# main.net
KiCad netlist of a schematic drawn in Altium Designer
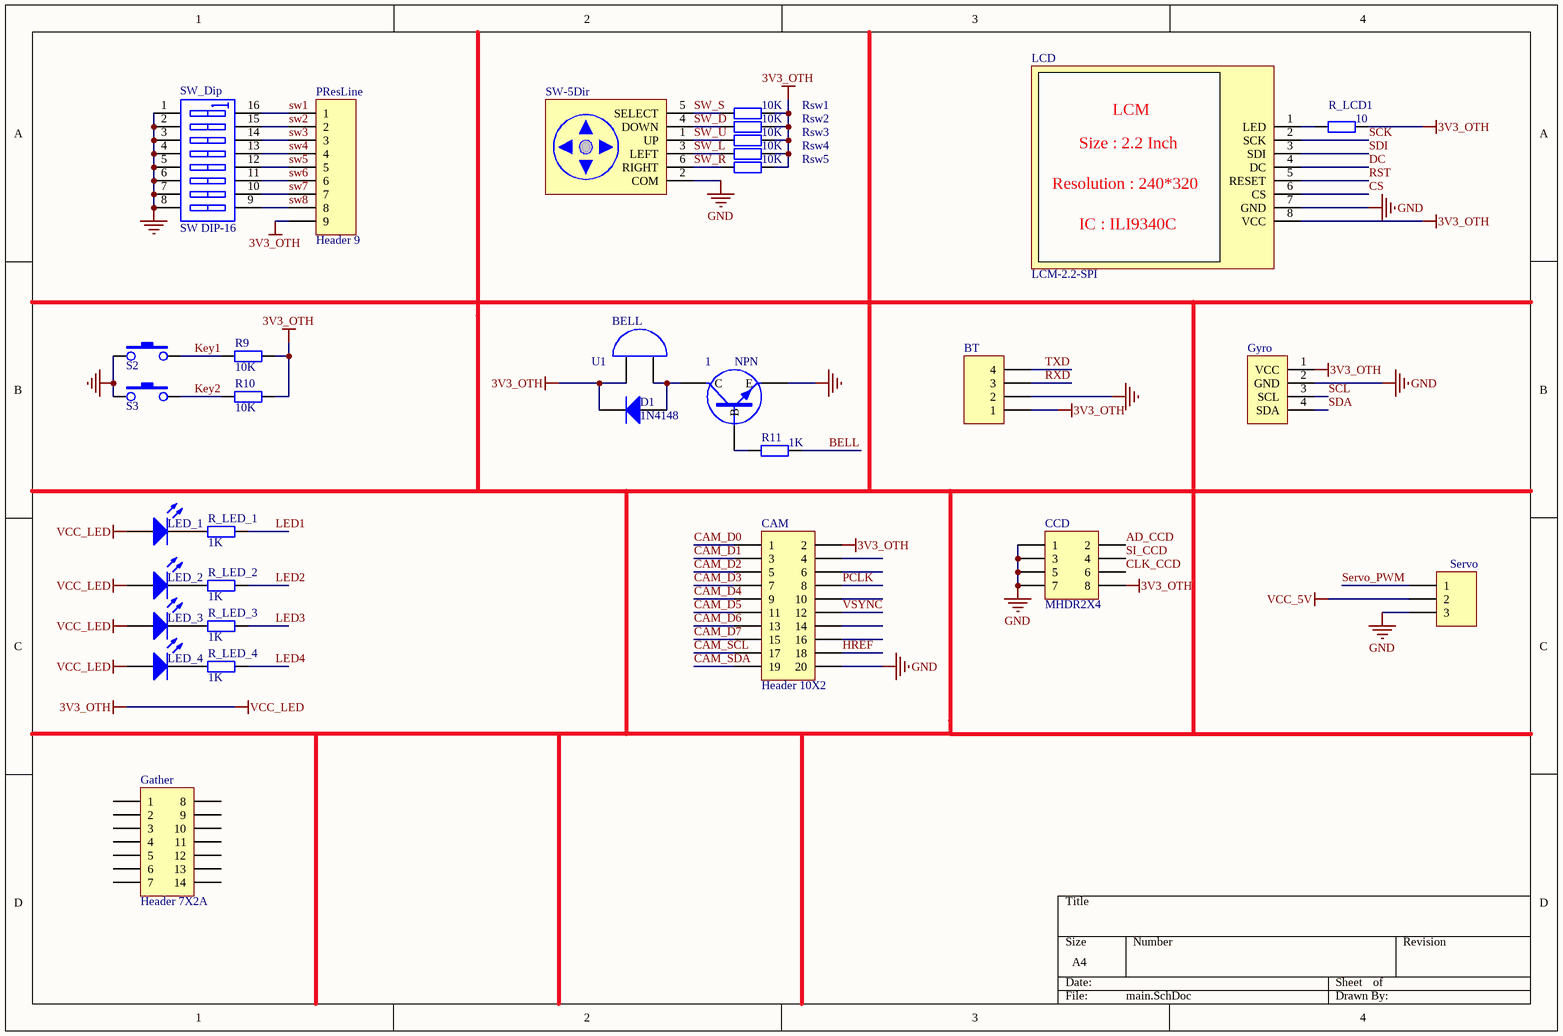
[diagram p0: main.SchDoc]

(export (version "E")
  (design (tool "Eeschema 10.0.6"))
  (components
    (comp (ref "1") (value "NPN") (footprint "BEC_123_S") (libsource (lib "lichao_Library") (part "NPN")))
    (comp (ref "BT")
      (value "Header 4")
      (footprint "HDR1X4")
      (description "Header, 4-Pin")
      (fields (field (name "PUBLISHER") "Altium Limited"))
      (libsource (lib "Miscellaneous Connectors") (part "Header 4"))
    )
    (comp (ref "CAM")
      (value "Header 10X2")
      (footprint "Camer")
      (description "Header, 10-Pin, Dual row")
      (fields (field (name "PUBLISHER") "Altium Limited"))
      (libsource (lib "Miscellaneous Connectors") (part "Header 10X2"))
    )
    (comp (ref "CCD")
      (value "MHDR2X4")
      (footprint "CCD")
      (description "Header, 4-Pin, Dual row")
      (fields (field (name "PUBLISHER") "Altium Limited"))
      (libsource (lib "lichao_Library") (part "MHDR2X4"))
    )
    (comp (ref "D1")
      (value "1N4148")
      (footprint "1N4148")
      (fields (field (name "PUBLISHER") "Altium Limited"))
      (libsource (lib "YMYPcbLib") (part "Diode"))
    )
    (comp (ref "Gather")
      (value "Header 7X2A")
      (footprint "HDR2X7_CEN")
      (description "Header, 7-Pin, Dual row")
      (fields (field (name "PUBLISHER") "Altium Limited"))
      (libsource (lib "Miscellaneous Connectors") (part "Header 7X2A"))
    )
    (comp (ref "Gyro") (value "Gyro") (footprint "GYRO") (libsource (lib "lichao_Library") (part "Gyro")))
    (comp (ref "LCD")
      (value "LCM-2.2-SPI")
      (footprint "LCD")
      (description "LCM 2.2inch SPI")
      (fields (field (name "PUBLISHER") "Altium Limited"))
      (libsource (lib "mine") (part "LCM-2.2-SPI"))
    )
    (comp (ref "LED_1")
      (value "LED")
      (footprint "0805-S")
      (description "Typical INFRARED GaAs LED")
      (fields (field (name "PUBLISHER") "Altium Limited"))
      (libsource (lib "Miscellaneous Devices") (part "LED0"))
    )
    (comp (ref "LED_2")
      (value "LED")
      (footprint "0805-S")
      (description "Typical INFRARED GaAs LED")
      (fields (field (name "PUBLISHER") "Altium Limited"))
      (libsource (lib "Miscellaneous Devices") (part "LED0"))
    )
    (comp (ref "LED_3")
      (value "LED")
      (footprint "0805-S")
      (description "Typical INFRARED GaAs LED")
      (fields (field (name "PUBLISHER") "Altium Limited"))
      (libsource (lib "Miscellaneous Devices") (part "LED0"))
    )
    (comp (ref "LED_4")
      (value "LED")
      (footprint "0805-S")
      (description "Typical INFRARED GaAs LED")
      (fields (field (name "PUBLISHER") "Altium Limited"))
      (libsource (lib "Miscellaneous Devices") (part "LED0"))
    )
    (comp (ref "PResLine")
      (value "Header 9")
      (footprint "HDR1X9")
      (description "Header, 9-Pin")
      (fields (field (name "PUBLISHER") "Altium Limited"))
      (libsource (lib "Miscellaneous Connectors") (part "Header 9"))
    )
    (comp (ref "R9")
      (value "10K")
      (footprint "0805-S")
      (description "Resistor")
      (fields (field (name "PUBLISHER") "Altium Limited"))
      (libsource (lib "") (part "Res2_1"))
    )
    (comp (ref "R10")
      (value "10K")
      (footprint "0805-S")
      (description "Resistor")
      (fields (field (name "PUBLISHER") "Altium Limited"))
      (libsource (lib "") (part "Res2_1"))
    )
    (comp (ref "R11")
      (value "1K")
      (footprint "0805-S")
      (description "Resistor")
      (fields (field (name "PUBLISHER") "Altium Limited"))
      (libsource (lib "Miscellaneous Devices") (part "Res2"))
    )
    (comp (ref "Rsw1")
      (value "10K")
      (footprint "0805-S")
      (description "Resistor")
      (fields (field (name "PUBLISHER") "Altium Limited"))
      (libsource (lib "Miscellaneous Devices") (part "Res2"))
    )
    (comp (ref "Rsw2")
      (value "10K")
      (footprint "0805-S")
      (description "Resistor")
      (fields (field (name "PUBLISHER") "Altium Limited"))
      (libsource (lib "Miscellaneous Devices") (part "Res2"))
    )
    (comp (ref "Rsw3")
      (value "10K")
      (footprint "0805-S")
      (description "Resistor")
      (fields (field (name "PUBLISHER") "Altium Limited"))
      (libsource (lib "Miscellaneous Devices") (part "Res2"))
    )
    (comp (ref "Rsw4")
      (value "10K")
      (footprint "0805-S")
      (description "Resistor")
      (fields (field (name "PUBLISHER") "Altium Limited"))
      (libsource (lib "Miscellaneous Devices") (part "Res2"))
    )
    (comp (ref "Rsw5")
      (value "10K")
      (footprint "0805-S")
      (description "Resistor")
      (fields (field (name "PUBLISHER") "Altium Limited"))
      (libsource (lib "Miscellaneous Devices") (part "Res2"))
    )
    (comp (ref "R_LCD1")
      (value "10")
      (footprint "0805-S")
      (description "Resistor")
      (fields (field (name "PUBLISHER") "Altium Limited"))
      (libsource (lib "") (part "Res2_1"))
    )
    (comp (ref "R_LED_1")
      (value "1K")
      (footprint "0805-S")
      (description "Resistor")
      (fields (field (name "PUBLISHER") "Altium Limited"))
      (libsource (lib "") (part "Res2_2"))
    )
    (comp (ref "R_LED_2")
      (value "1K")
      (footprint "0805-S")
      (description "Resistor")
      (fields (field (name "PUBLISHER") "Altium Limited"))
      (libsource (lib "") (part "Res2_2"))
    )
    (comp (ref "R_LED_3")
      (value "1K")
      (footprint "0805-S")
      (description "Resistor")
      (fields (field (name "PUBLISHER") "Altium Limited"))
      (libsource (lib "") (part "Res2_2"))
    )
    (comp (ref "R_LED_4")
      (value "1K")
      (footprint "0805-S")
      (description "Resistor")
      (fields (field (name "PUBLISHER") "Altium Limited"))
      (libsource (lib "") (part "Res2_2"))
    )
    (comp (ref "S2") (value "SW-PB") (footprint "key-press") (libsource (lib "*") (part "SW-PB")))
    (comp (ref "S3") (value "SW-PB") (footprint "key-press") (libsource (lib "*") (part "SW-PB")))
    (comp (ref "Servo")
      (value "Ser_head")
      (footprint "HDR1X3")
      (description "Header, 3-Pin")
      (fields (field (name "PUBLISHER") "Altium Limited"))
      (libsource (lib "Miscellaneous Connectors") (part "Header 3"))
    )
    (comp (ref "SW-5Dir")
      (value "SW-5dir")
      (footprint "SW-5dir")
      (description "2pin_GND")
      (fields (field (name "PUBLISHER") "Altium Limited"))
      (libsource (lib "lichao_Library") (part "SW-5dir"))
    )
    (comp (ref "SW_Dip")
      (value "SW DIP-16")
      (footprint "DIP16")
      (description "DIP Switch, 8 Position, SPST")
      (fields (field (name "PUBLISHER") "Altium Limited"))
      (libsource (lib "Miscellaneous Devices") (part "SW DIP-8"))
    )
    (comp (ref "U1")
      (value "BELL")
      (footprint "BEEP")
      (description "Bell")
      (libsource (lib "*") (part "BELL"))
    )
  )
  (nets
    (net (code "1") (name "/AD_CCD") (class "Default")
      (node (ref "CCD") (pin "2") (pinfunction "2_2") (pintype "passive"))
    )
    (net (code "2") (name "/BELL") (class "Default")
      (node (ref "R11") (pin "2") (pinfunction "2_2") (pintype "passive"))
    )
    (net (code "3") (name "/CAM_D0") (class "Default")
      (node (ref "CAM") (pin "1") (pinfunction "1_1") (pintype "passive"))
    )
    (net (code "4") (name "/CAM_D1") (class "Default")
      (node (ref "CAM") (pin "3") (pinfunction "3_3") (pintype "passive"))
    )
    (net (code "5") (name "/CAM_D2") (class "Default")
      (node (ref "CAM") (pin "5") (pinfunction "5_5") (pintype "passive"))
    )
    (net (code "6") (name "/CAM_D3") (class "Default")
      (node (ref "CAM") (pin "7") (pinfunction "7_7") (pintype "passive"))
    )
    (net (code "7") (name "/CAM_D4") (class "Default")
      (node (ref "CAM") (pin "9") (pinfunction "9_9") (pintype "passive"))
    )
    (net (code "8") (name "/CAM_D5") (class "Default")
      (node (ref "CAM") (pin "11") (pinfunction "11_11") (pintype "passive"))
    )
    (net (code "9") (name "/CAM_D6") (class "Default")
      (node (ref "CAM") (pin "13") (pinfunction "13_13") (pintype "passive"))
    )
    (net (code "10") (name "/CAM_D7") (class "Default")
      (node (ref "CAM") (pin "15") (pinfunction "15_15") (pintype "passive"))
    )
    (net (code "11") (name "/CAM_SCL") (class "Default")
      (node (ref "CAM") (pin "17") (pinfunction "17_17") (pintype "passive"))
    )
    (net (code "12") (name "/CAM_SDA") (class "Default")
      (node (ref "CAM") (pin "19") (pinfunction "19_19") (pintype "passive"))
    )
    (net (code "13") (name "/CLK_CCD") (class "Default")
      (node (ref "CCD") (pin "6") (pinfunction "6_6") (pintype "passive"))
    )
    (net (code "14") (name "/CS") (class "Default")
      (node (ref "LCD") (pin "6") (pinfunction "CS_6") (pintype "passive"))
    )
    (net (code "15") (name "/DC") (class "Default")
      (node (ref "LCD") (pin "4") (pinfunction "DC_4") (pintype "passive"))
    )
    (net (code "16") (name "/HREF") (class "Default")
      (node (ref "CAM") (pin "18") (pinfunction "18_18") (pintype "passive"))
    )
    (net (code "17") (name "/Key1") (class "Default")
      (node (ref "R9") (pin "2") (pinfunction "2_2") (pintype "passive"))
      (node (ref "S2") (pin "2") (pinfunction "2_2") (pintype "passive"))
    )
    (net (code "18") (name "/Key2") (class "Default")
      (node (ref "R10") (pin "2") (pinfunction "2_2") (pintype "passive"))
      (node (ref "S3") (pin "2") (pinfunction "2_2") (pintype "passive"))
    )
    (net (code "19") (name "/LED1") (class "Default")
      (node (ref "R_LED_1") (pin "1") (pinfunction "1_1") (pintype "passive"))
    )
    (net (code "20") (name "/LED2") (class "Default")
      (node (ref "R_LED_2") (pin "1") (pinfunction "1_1") (pintype "passive"))
    )
    (net (code "21") (name "/LED3") (class "Default")
      (node (ref "R_LED_3") (pin "1") (pinfunction "1_1") (pintype "passive"))
    )
    (net (code "22") (name "/LED4") (class "Default")
      (node (ref "R_LED_4") (pin "1") (pinfunction "1_1") (pintype "passive"))
    )
    (net (code "23") (name "/PCLK") (class "Default")
      (node (ref "CAM") (pin "8") (pinfunction "8_8") (pintype "passive"))
    )
    (net (code "24") (name "/RST") (class "Default")
      (node (ref "LCD") (pin "5") (pinfunction "RESET_5") (pintype "passive"))
    )
    (net (code "25") (name "/RXD") (class "Default")
      (node (ref "BT") (pin "3") (pinfunction "3_3") (pintype "passive"))
    )
    (net (code "26") (name "/SCK") (class "Default")
      (node (ref "LCD") (pin "2") (pinfunction "SCK_2") (pintype "passive"))
    )
    (net (code "27") (name "/SCL") (class "Default")
      (node (ref "Gyro") (pin "3") (pinfunction "SCL_3") (pintype "passive"))
    )
    (net (code "28") (name "/SDA") (class "Default")
      (node (ref "Gyro") (pin "4") (pinfunction "SDA_4") (pintype "passive"))
    )
    (net (code "29") (name "/SDI") (class "Default")
      (node (ref "LCD") (pin "3") (pinfunction "SDI_3") (pintype "passive"))
    )
    (net (code "30") (name "/SI_CCD") (class "Default")
      (node (ref "CCD") (pin "4") (pinfunction "4_4") (pintype "passive"))
    )
    (net (code "31") (name "/SW_D") (class "Default")
      (node (ref "Rsw2") (pin "1") (pinfunction "1_1") (pintype "passive"))
      (node (ref "SW-5Dir") (pin "4") (pinfunction "DOWN_4") (pintype "passive"))
    )
    (net (code "32") (name "/SW_L") (class "Default")
      (node (ref "Rsw4") (pin "1") (pinfunction "1_1") (pintype "passive"))
      (node (ref "SW-5Dir") (pin "3") (pinfunction "LEFT_3") (pintype "passive"))
    )
    (net (code "33") (name "/SW_R") (class "Default")
      (node (ref "Rsw5") (pin "1") (pinfunction "1_1") (pintype "passive"))
      (node (ref "SW-5Dir") (pin "6") (pinfunction "RIGHT_6") (pintype "passive"))
    )
    (net (code "34") (name "/SW_S") (class "Default")
      (node (ref "Rsw1") (pin "1") (pinfunction "1_1") (pintype "passive"))
      (node (ref "SW-5Dir") (pin "5") (pinfunction "SELECT_5") (pintype "passive"))
    )
    (net (code "35") (name "/SW_U") (class "Default")
      (node (ref "Rsw3") (pin "1") (pinfunction "1_1") (pintype "passive"))
      (node (ref "SW-5Dir") (pin "1") (pinfunction "UP_1") (pintype "passive"))
    )
    (net (code "36") (name "/Servo_PWM") (class "Default")
      (node (ref "Servo") (pin "1") (pinfunction "1_1") (pintype "passive"))
    )
    (net (code "37") (name "/TXD") (class "Default")
      (node (ref "BT") (pin "4") (pinfunction "4_4") (pintype "passive"))
    )
    (net (code "38") (name "/VSYNC") (class "Default")
      (node (ref "CAM") (pin "12") (pinfunction "12_12") (pintype "passive"))
    )
    (net (code "39") (name "/sw1") (class "Default")
      (node (ref "PResLine") (pin "1") (pinfunction "1_1") (pintype "passive"))
      (node (ref "SW_Dip") (pin "16") (pinfunction "B1_16") (pintype "passive"))
    )
    (net (code "40") (name "/sw2") (class "Default")
      (node (ref "PResLine") (pin "2") (pinfunction "2_2") (pintype "passive"))
      (node (ref "SW_Dip") (pin "15") (pinfunction "B2_15") (pintype "passive"))
    )
    (net (code "41") (name "/sw3") (class "Default")
      (node (ref "PResLine") (pin "3") (pinfunction "3_3") (pintype "passive"))
      (node (ref "SW_Dip") (pin "14") (pinfunction "B3_14") (pintype "passive"))
    )
    (net (code "42") (name "/sw4") (class "Default")
      (node (ref "PResLine") (pin "4") (pinfunction "4_4") (pintype "passive"))
      (node (ref "SW_Dip") (pin "13") (pinfunction "B4_13") (pintype "passive"))
    )
    (net (code "43") (name "/sw5") (class "Default")
      (node (ref "PResLine") (pin "5") (pinfunction "5_5") (pintype "passive"))
      (node (ref "SW_Dip") (pin "12") (pinfunction "B5_12") (pintype "passive"))
    )
    (net (code "44") (name "/sw6") (class "Default")
      (node (ref "PResLine") (pin "6") (pinfunction "6_6") (pintype "passive"))
      (node (ref "SW_Dip") (pin "11") (pinfunction "B6_11") (pintype "passive"))
    )
    (net (code "45") (name "/sw7") (class "Default")
      (node (ref "PResLine") (pin "7") (pinfunction "7_7") (pintype "passive"))
      (node (ref "SW_Dip") (pin "10") (pinfunction "B7_10") (pintype "passive"))
    )
    (net (code "46") (name "/sw8") (class "Default")
      (node (ref "PResLine") (pin "8") (pinfunction "8_8") (pintype "passive"))
      (node (ref "SW_Dip") (pin "9") (pinfunction "B8_9") (pintype "passive"))
    )
    (net (code "47") (name "3V3_OTH") (class "Default")
      (node (ref "BT") (pin "1") (pinfunction "1_1") (pintype "passive"))
      (node (ref "CAM") (pin "2") (pinfunction "2_2") (pintype "passive"))
      (node (ref "CCD") (pin "8") (pinfunction "8_8") (pintype "passive"))
      (node (ref "D1") (pin "2") (pinfunction "K_2") (pintype "passive"))
      (node (ref "Gyro") (pin "1") (pinfunction "VCC_1") (pintype "passive"))
      (node (ref "LCD") (pin "8") (pinfunction "VCC_8") (pintype "passive"))
      (node (ref "LED_1") (pin "1") (pinfunction "A_1") (pintype "passive"))
      (node (ref "LED_2") (pin "1") (pinfunction "A_1") (pintype "passive"))
      (node (ref "LED_3") (pin "1") (pinfunction "A_1") (pintype "passive"))
      (node (ref "LED_4") (pin "1") (pinfunction "A_1") (pintype "passive"))
      (node (ref "PResLine") (pin "9") (pinfunction "9_9") (pintype "passive"))
      (node (ref "R10") (pin "1") (pinfunction "1_1") (pintype "passive"))
      (node (ref "R9") (pin "1") (pinfunction "1_1") (pintype "passive"))
      (node (ref "R_LCD1") (pin "1") (pinfunction "1_1") (pintype "passive"))
      (node (ref "Rsw1") (pin "2") (pinfunction "2_2") (pintype "passive"))
      (node (ref "Rsw2") (pin "2") (pinfunction "2_2") (pintype "passive"))
      (node (ref "Rsw3") (pin "2") (pinfunction "2_2") (pintype "passive"))
      (node (ref "Rsw4") (pin "2") (pinfunction "2_2") (pintype "passive"))
      (node (ref "Rsw5") (pin "2") (pinfunction "2_2") (pintype "passive"))
      (node (ref "U1") (pin "1") (pinfunction "A_1") (pintype "passive"))
    )
    (net (code "48") (name "GND") (class "Default")
      (node (ref "1") (pin "2") (pinfunction "E_2") (pintype "passive"))
      (node (ref "BT") (pin "2") (pinfunction "2_2") (pintype "passive"))
      (node (ref "CAM") (pin "20") (pinfunction "20_20") (pintype "passive"))
      (node (ref "CCD") (pin "1") (pinfunction "1_1") (pintype "passive"))
      (node (ref "CCD") (pin "3") (pinfunction "3_3") (pintype "passive"))
      (node (ref "CCD") (pin "5") (pinfunction "5_5") (pintype "passive"))
      (node (ref "CCD") (pin "7") (pinfunction "7_7") (pintype "passive"))
      (node (ref "Gyro") (pin "2") (pinfunction "GND_2") (pintype "passive"))
      (node (ref "LCD") (pin "7") (pinfunction "GND_7") (pintype "passive"))
      (node (ref "S2") (pin "1") (pinfunction "1_1") (pintype "passive"))
      (node (ref "S3") (pin "1") (pinfunction "1_1") (pintype "passive"))
      (node (ref "SW-5Dir") (pin "2") (pinfunction "COM_2") (pintype "passive"))
      (node (ref "SW_Dip") (pin "1") (pinfunction "A1_1") (pintype "passive"))
      (node (ref "SW_Dip") (pin "2") (pinfunction "A2_2") (pintype "passive"))
      (node (ref "SW_Dip") (pin "3") (pinfunction "A3_3") (pintype "passive"))
      (node (ref "SW_Dip") (pin "4") (pinfunction "A4_4") (pintype "passive"))
      (node (ref "SW_Dip") (pin "5") (pinfunction "A5_5") (pintype "passive"))
      (node (ref "SW_Dip") (pin "6") (pinfunction "A6_6") (pintype "passive"))
      (node (ref "SW_Dip") (pin "7") (pinfunction "A7_7") (pintype "passive"))
      (node (ref "SW_Dip") (pin "8") (pinfunction "A8_8") (pintype "passive"))
      (node (ref "Servo") (pin "3") (pinfunction "3_3") (pintype "passive"))
    )
    (net (code "49") (name "Net-(1-B)") (class "Default")
      (node (ref "1") (pin "1") (pinfunction "B_1") (pintype "passive"))
      (node (ref "R11") (pin "1") (pinfunction "1_1") (pintype "passive"))
    )
    (net (code "50") (name "Net-(1-C)") (class "Default")
      (node (ref "1") (pin "3") (pinfunction "C_3") (pintype "passive"))
      (node (ref "D1") (pin "1") (pinfunction "A_1") (pintype "passive"))
      (node (ref "U1") (pin "2") (pinfunction "B_2") (pintype "passive"))
    )
    (net (code "51") (name "Net-(LCD-LED)") (class "Default")
      (node (ref "LCD") (pin "1") (pinfunction "LED_1") (pintype "passive"))
      (node (ref "R_LCD1") (pin "2") (pinfunction "2_2") (pintype "passive"))
    )
    (net (code "52") (name "Net-(LED_1-K)") (class "Default")
      (node (ref "LED_1") (pin "2") (pinfunction "K_2") (pintype "passive"))
      (node (ref "R_LED_1") (pin "2") (pinfunction "2_2") (pintype "passive"))
    )
    (net (code "53") (name "Net-(LED_2-K)") (class "Default")
      (node (ref "LED_2") (pin "2") (pinfunction "K_2") (pintype "passive"))
      (node (ref "R_LED_2") (pin "2") (pinfunction "2_2") (pintype "passive"))
    )
    (net (code "54") (name "Net-(LED_3-K)") (class "Default")
      (node (ref "LED_3") (pin "2") (pinfunction "K_2") (pintype "passive"))
      (node (ref "R_LED_3") (pin "2") (pinfunction "2_2") (pintype "passive"))
    )
    (net (code "55") (name "Net-(LED_4-K)") (class "Default")
      (node (ref "LED_4") (pin "2") (pinfunction "K_2") (pintype "passive"))
      (node (ref "R_LED_4") (pin "2") (pinfunction "2_2") (pintype "passive"))
    )
    (net (code "56") (name "VCC_5V") (class "Default")
      (node (ref "Servo") (pin "2") (pinfunction "2_2") (pintype "passive"))
    )
    (net (code "57") (name "unconnected-(CAM-Pad4)") (class "Default")
      (node (ref "CAM") (pin "4") (pinfunction "4_4") (pintype "passive"))
    )
    (net (code "58") (name "unconnected-(CAM-Pad6)") (class "Default")
      (node (ref "CAM") (pin "6") (pinfunction "6_6") (pintype "passive"))
    )
    (net (code "59") (name "unconnected-(CAM-Pad10)") (class "Default")
      (node (ref "CAM") (pin "10") (pinfunction "10_10") (pintype "passive"))
    )
    (net (code "60") (name "unconnected-(CAM-Pad14)") (class "Default")
      (node (ref "CAM") (pin "14") (pinfunction "14_14") (pintype "passive"))
    )
    (net (code "61") (name "unconnected-(CAM-Pad16)") (class "Default")
      (node (ref "CAM") (pin "16") (pinfunction "16_16") (pintype "passive"))
    )
    (net (code "62") (name "unconnected-(Gather-Pad1)") (class "Default")
      (node (ref "Gather") (pin "1") (pinfunction "1_1") (pintype "passive"))
    )
    (net (code "63") (name "unconnected-(Gather-Pad2)") (class "Default")
      (node (ref "Gather") (pin "2") (pinfunction "2_2") (pintype "passive"))
    )
    (net (code "64") (name "unconnected-(Gather-Pad3)") (class "Default")
      (node (ref "Gather") (pin "3") (pinfunction "3_3") (pintype "passive"))
    )
    (net (code "65") (name "unconnected-(Gather-Pad4)") (class "Default")
      (node (ref "Gather") (pin "4") (pinfunction "4_4") (pintype "passive"))
    )
    (net (code "66") (name "unconnected-(Gather-Pad5)") (class "Default")
      (node (ref "Gather") (pin "5") (pinfunction "5_5") (pintype "passive"))
    )
    (net (code "67") (name "unconnected-(Gather-Pad6)") (class "Default")
      (node (ref "Gather") (pin "6") (pinfunction "6_6") (pintype "passive"))
    )
    (net (code "68") (name "unconnected-(Gather-Pad7)") (class "Default")
      (node (ref "Gather") (pin "7") (pinfunction "7_7") (pintype "passive"))
    )
    (net (code "69") (name "unconnected-(Gather-Pad8)") (class "Default")
      (node (ref "Gather") (pin "8") (pinfunction "8_8") (pintype "passive"))
    )
    (net (code "70") (name "unconnected-(Gather-Pad9)") (class "Default")
      (node (ref "Gather") (pin "9") (pinfunction "9_9") (pintype "passive"))
    )
    (net (code "71") (name "unconnected-(Gather-Pad10)") (class "Default")
      (node (ref "Gather") (pin "10") (pinfunction "10_10") (pintype "passive"))
    )
    (net (code "72") (name "unconnected-(Gather-Pad11)") (class "Default")
      (node (ref "Gather") (pin "11") (pinfunction "11_11") (pintype "passive"))
    )
    (net (code "73") (name "unconnected-(Gather-Pad12)") (class "Default")
      (node (ref "Gather") (pin "12") (pinfunction "12_12") (pintype "passive"))
    )
    (net (code "74") (name "unconnected-(Gather-Pad13)") (class "Default")
      (node (ref "Gather") (pin "13") (pinfunction "13_13") (pintype "passive"))
    )
    (net (code "75") (name "unconnected-(Gather-Pad14)") (class "Default")
      (node (ref "Gather") (pin "14") (pinfunction "14_14") (pintype "passive"))
    )
  )
)
